# IDC2BNC.net
KiCad netlist of a schematic drawn in Altium Designer
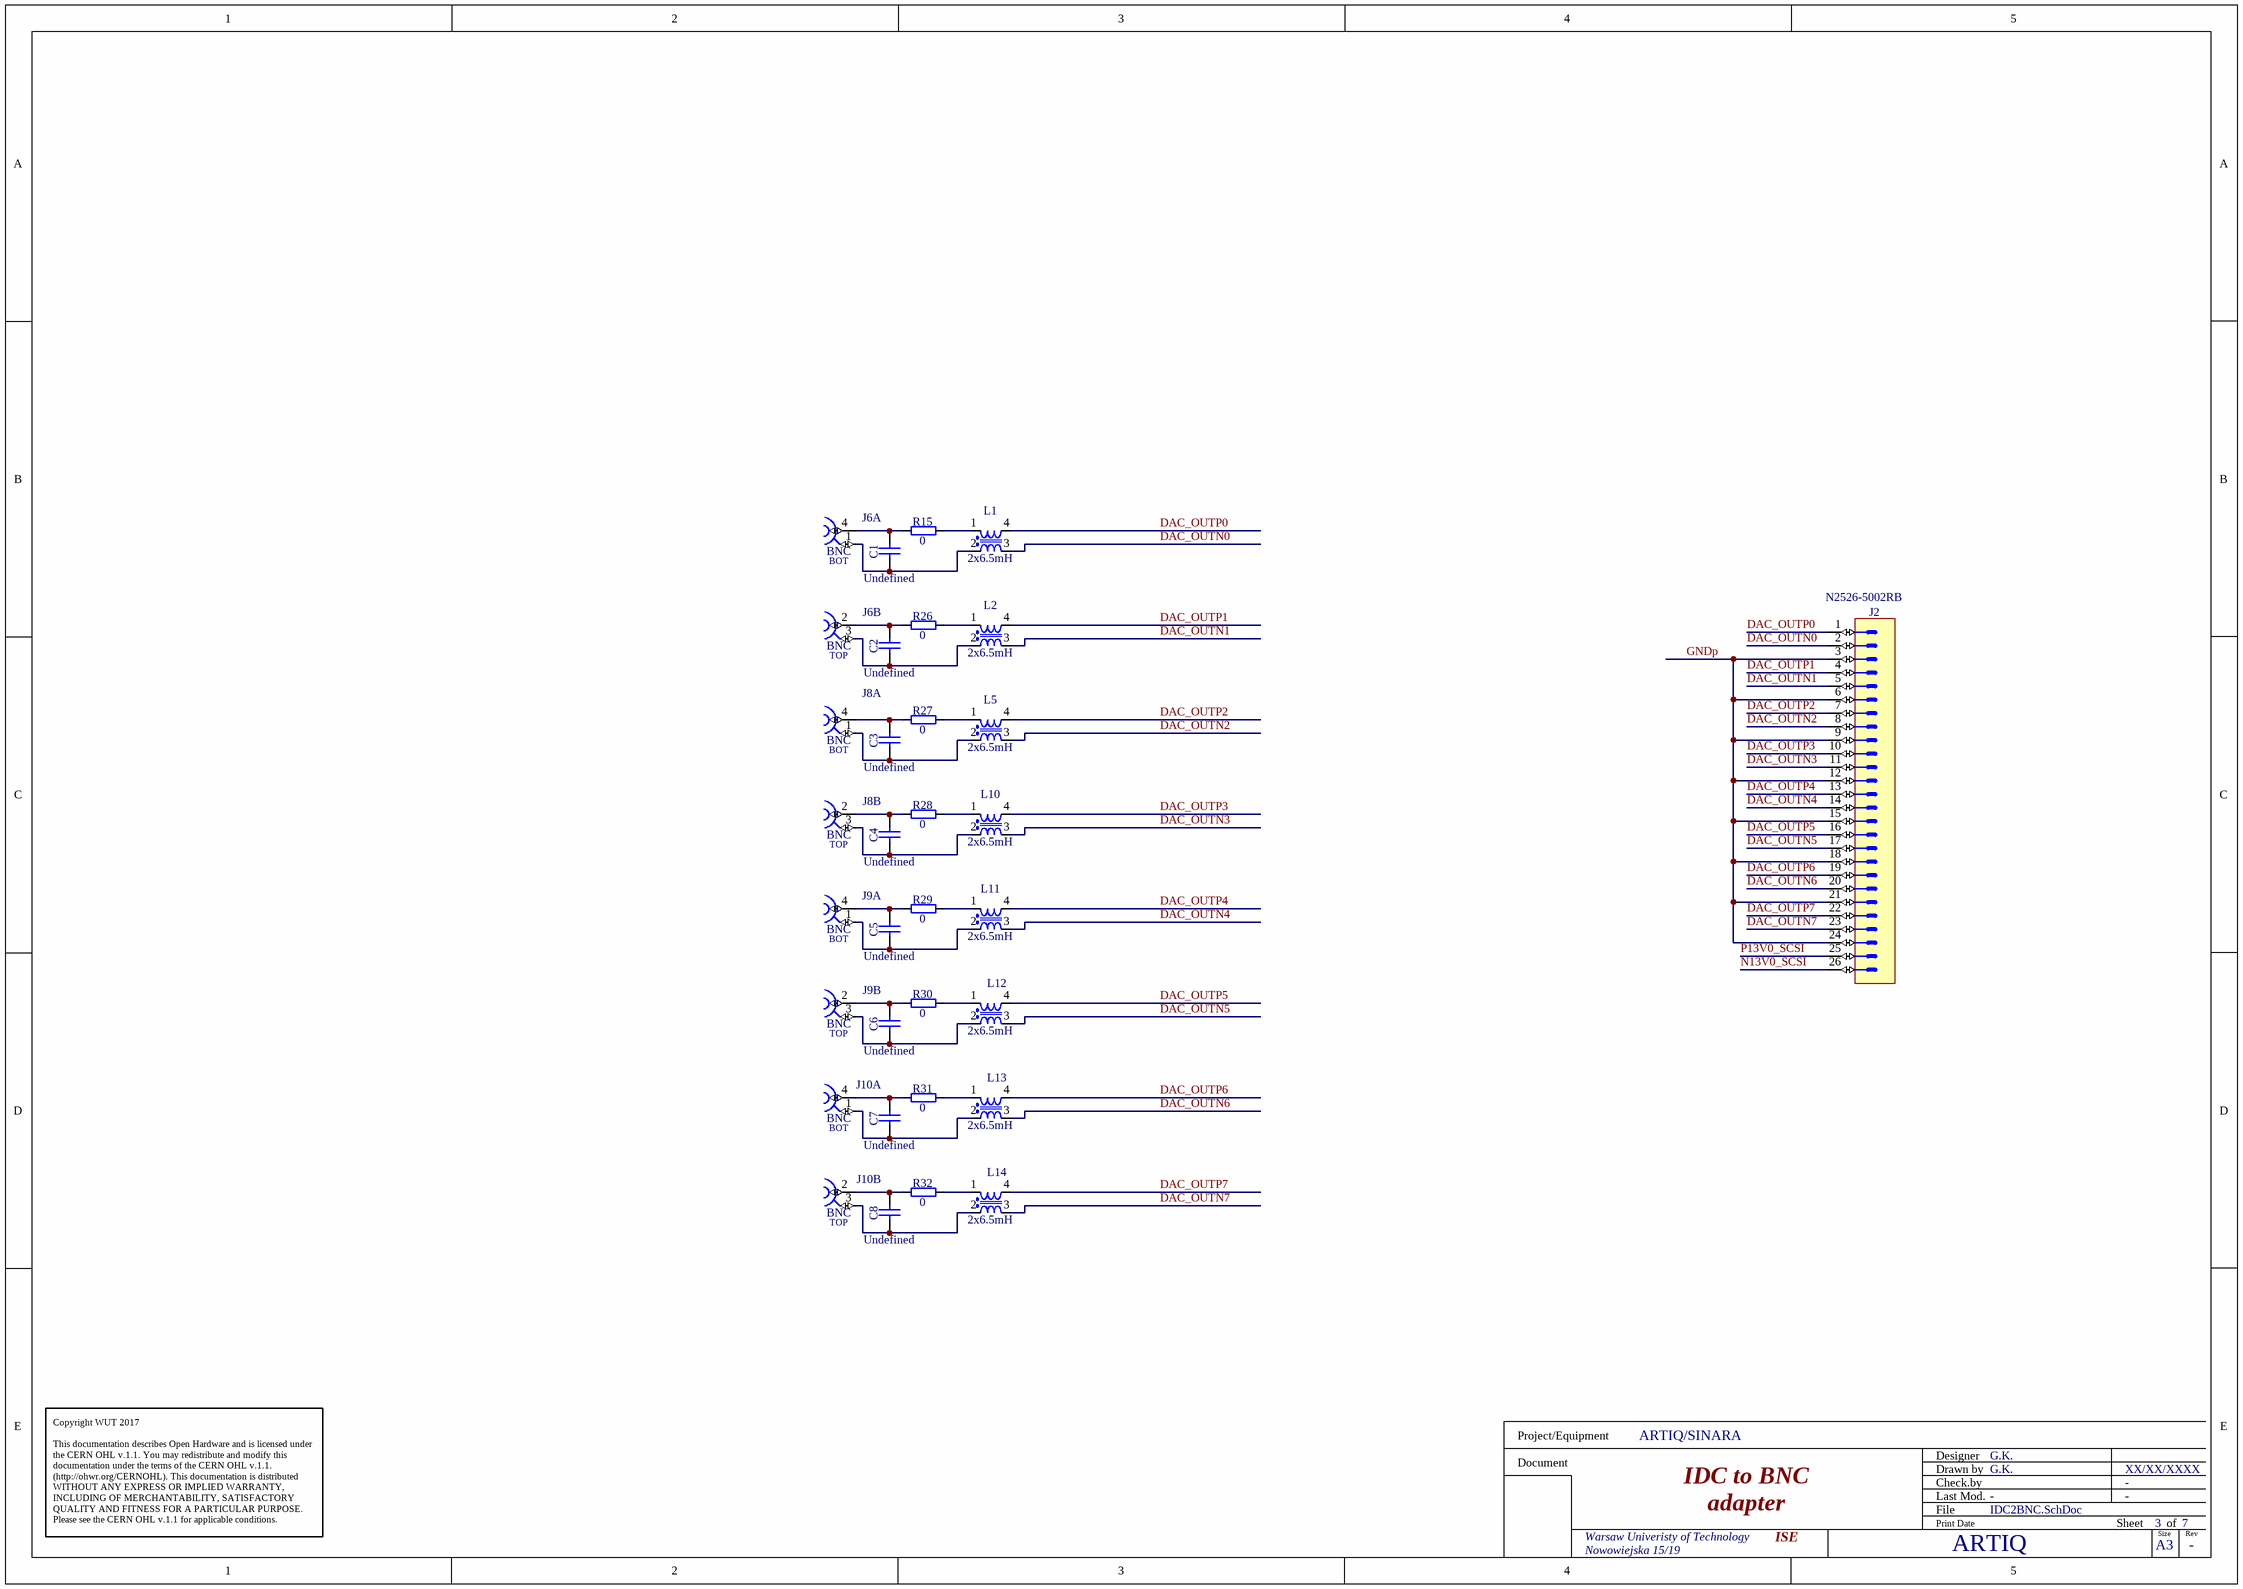
[diagram p0: IDC2BNC.SchDoc]

(export (version "E")
  (design (tool "Eeschema 10.0.6"))
  (components
    (comp (ref "C1")
      (value "Undefined")
      (footprint "CAPC2012X135N")
      (description "Non-polarised capacitor")
      (fields (field (name "PART NUMBER") "CC0805_NO-VALUE") (field (name "AUTHOR") "CERN DEM JLC"))
      (libsource (lib "Capacitors") (part "Capacitor - non polarized"))
    )
    (comp (ref "C2")
      (value "Undefined")
      (footprint "CAPC2012X135N")
      (description "Non-polarised capacitor")
      (fields (field (name "PART NUMBER") "CC0805_NO-VALUE") (field (name "AUTHOR") "CERN DEM JLC"))
      (libsource (lib "Capacitors") (part "Capacitor - non polarized"))
    )
    (comp (ref "C3")
      (value "Undefined")
      (footprint "CAPC2012X135N")
      (description "Non-polarised capacitor")
      (fields (field (name "PART NUMBER") "CC0805_NO-VALUE") (field (name "AUTHOR") "CERN DEM JLC"))
      (libsource (lib "Capacitors") (part "Capacitor - non polarized"))
    )
    (comp (ref "C4")
      (value "Undefined")
      (footprint "CAPC2012X135N")
      (description "Non-polarised capacitor")
      (fields (field (name "PART NUMBER") "CC0805_NO-VALUE") (field (name "AUTHOR") "CERN DEM JLC"))
      (libsource (lib "Capacitors") (part "Capacitor - non polarized"))
    )
    (comp (ref "C5")
      (value "Undefined")
      (footprint "CAPC2012X135N")
      (description "Non-polarised capacitor")
      (fields (field (name "PART NUMBER") "CC0805_NO-VALUE") (field (name "AUTHOR") "CERN DEM JLC"))
      (libsource (lib "Capacitors") (part "Capacitor - non polarized"))
    )
    (comp (ref "C6")
      (value "Undefined")
      (footprint "CAPC2012X135N")
      (description "Non-polarised capacitor")
      (fields (field (name "PART NUMBER") "CC0805_NO-VALUE") (field (name "AUTHOR") "CERN DEM JLC"))
      (libsource (lib "Capacitors") (part "Capacitor - non polarized"))
    )
    (comp (ref "C7")
      (value "Undefined")
      (footprint "CAPC2012X135N")
      (description "Non-polarised capacitor")
      (fields (field (name "PART NUMBER") "CC0805_NO-VALUE") (field (name "AUTHOR") "CERN DEM JLC"))
      (libsource (lib "Capacitors") (part "Capacitor - non polarized"))
    )
    (comp (ref "C8")
      (value "Undefined")
      (footprint "CAPC2012X135N")
      (description "Non-polarised capacitor")
      (fields (field (name "PART NUMBER") "CC0805_NO-VALUE") (field (name "AUTHOR") "CERN DEM JLC"))
      (libsource (lib "Capacitors") (part "Capacitor - non polarized"))
    )
    (comp (ref "J2")
      (value "Header 26")
      (footprint "3M_N2526-5002RB")
      (description "Connector 26 Male")
      (fields
        (field (name "PART NUMBER") "3M_N2526-5002RB")
        (field (name "MANUFACTURER") "3M")
        (field (name "MANUFACTURER PART NUMBER") "N2526-5002RB")
        (field (name "AUTHOR") "CERN DEM JLC")
      )
      (libsource (lib "Connectors") (part "Connector 26 Male"))
    )
    (comp (ref "J6")
      (value "BNC")
      (footprint "BOMAR_364A2595")
      (description "Dual Right Angle 50 Ohm BNC Jack, White Valox Case")
      (fields
        (field (name "PART NUMBER") "BOMAR_364A2595")
        (field (name "MANUFACTURER") "BOMAR INTERCONNECT")
        (field (name "AUTHOR") "CERN DEM JLC")
      )
      (libsource (lib "Connectors") (part "BOMAR_364A2595"))
    )
    (comp (ref "J8")
      (value "BNC")
      (footprint "BOMAR_364A2595")
      (description "Dual Right Angle 50 Ohm BNC Jack, White Valox Case")
      (fields
        (field (name "PART NUMBER") "BOMAR_364A2595")
        (field (name "MANUFACTURER") "BOMAR INTERCONNECT")
        (field (name "AUTHOR") "CERN DEM JLC")
      )
      (libsource (lib "Connectors") (part "BOMAR_364A2595"))
    )
    (comp (ref "J9")
      (value "BNC")
      (footprint "BOMAR_364A2595")
      (description "Dual Right Angle 50 Ohm BNC Jack, White Valox Case")
      (fields
        (field (name "PART NUMBER") "BOMAR_364A2595")
        (field (name "MANUFACTURER") "BOMAR INTERCONNECT")
        (field (name "AUTHOR") "CERN DEM JLC")
      )
      (libsource (lib "Connectors") (part "BOMAR_364A2595"))
    )
    (comp (ref "J10")
      (value "BNC")
      (footprint "BOMAR_364A2595")
      (description "Dual Right Angle 50 Ohm BNC Jack, White Valox Case")
      (fields
        (field (name "PART NUMBER") "BOMAR_364A2595")
        (field (name "MANUFACTURER") "BOMAR INTERCONNECT")
        (field (name "AUTHOR") "CERN DEM JLC")
      )
      (libsource (lib "Connectors") (part "BOMAR_364A2595"))
    )
    (comp (ref "L1")
      (value "2x6.5mH")
      (footprint "IND_WURTH_WE-SL2")
      (description "Inductor Common Mode")
      (fields
        (field (name "PART NUMBER") "IND_6.5MH_50%_WURTH_WE-SL2-744229")
        (field (name "POWER") "400mA")
        (field (name "AUTHOR") "CERN DEM JLC")
      )
      (libsource (lib "Inductors & Transformers") (part "Inductor Common Mode 1Dot-4 2Dot-3"))
    )
    (comp (ref "L2")
      (value "2x6.5mH")
      (footprint "IND_WURTH_WE-SL2")
      (description "Inductor Common Mode")
      (fields
        (field (name "PART NUMBER") "IND_6.5MH_50%_WURTH_WE-SL2-744229")
        (field (name "POWER") "400mA")
        (field (name "AUTHOR") "CERN DEM JLC")
      )
      (libsource (lib "Inductors & Transformers") (part "Inductor Common Mode 1Dot-4 2Dot-3"))
    )
    (comp (ref "L5")
      (value "2x6.5mH")
      (footprint "IND_WURTH_WE-SL2")
      (description "Inductor Common Mode")
      (fields
        (field (name "PART NUMBER") "IND_6.5MH_50%_WURTH_WE-SL2-744229")
        (field (name "POWER") "400mA")
        (field (name "AUTHOR") "CERN DEM JLC")
      )
      (libsource (lib "Inductors & Transformers") (part "Inductor Common Mode 1Dot-4 2Dot-3"))
    )
    (comp (ref "L10")
      (value "2x6.5mH")
      (footprint "IND_WURTH_WE-SL2")
      (description "Inductor Common Mode")
      (fields
        (field (name "PART NUMBER") "IND_6.5MH_50%_WURTH_WE-SL2-744229")
        (field (name "POWER") "400mA")
        (field (name "AUTHOR") "CERN DEM JLC")
      )
      (libsource (lib "Inductors & Transformers") (part "Inductor Common Mode 1Dot-4 2Dot-3"))
    )
    (comp (ref "L11")
      (value "2x6.5mH")
      (footprint "IND_WURTH_WE-SL2")
      (description "Inductor Common Mode")
      (fields
        (field (name "PART NUMBER") "IND_6.5MH_50%_WURTH_WE-SL2-744229")
        (field (name "POWER") "400mA")
        (field (name "AUTHOR") "CERN DEM JLC")
      )
      (libsource (lib "Inductors & Transformers") (part "Inductor Common Mode 1Dot-4 2Dot-3"))
    )
    (comp (ref "L12")
      (value "2x6.5mH")
      (footprint "IND_WURTH_WE-SL2")
      (description "Inductor Common Mode")
      (fields
        (field (name "PART NUMBER") "IND_6.5MH_50%_WURTH_WE-SL2-744229")
        (field (name "POWER") "400mA")
        (field (name "AUTHOR") "CERN DEM JLC")
      )
      (libsource (lib "Inductors & Transformers") (part "Inductor Common Mode 1Dot-4 2Dot-3"))
    )
    (comp (ref "L13")
      (value "2x6.5mH")
      (footprint "IND_WURTH_WE-SL2")
      (description "Inductor Common Mode")
      (fields
        (field (name "PART NUMBER") "IND_6.5MH_50%_WURTH_WE-SL2-744229")
        (field (name "POWER") "400mA")
        (field (name "AUTHOR") "CERN DEM JLC")
      )
      (libsource (lib "Inductors & Transformers") (part "Inductor Common Mode 1Dot-4 2Dot-3"))
    )
    (comp (ref "L14")
      (value "2x6.5mH")
      (footprint "IND_WURTH_WE-SL2")
      (description "Inductor Common Mode")
      (fields
        (field (name "PART NUMBER") "IND_6.5MH_50%_WURTH_WE-SL2-744229")
        (field (name "POWER") "400mA")
        (field (name "AUTHOR") "CERN DEM JLC")
      )
      (libsource (lib "Inductors & Transformers") (part "Inductor Common Mode 1Dot-4 2Dot-3"))
    )
    (comp (ref "R15")
      (value "0")
      (footprint "RESC1608X55N")
      (description "Resistor")
      (fields
        (field (name "PART NUMBER") "R0603_0R_JUMPER")
        (field (name "MANUFACTURER") "GENERIC")
        (field (name "AUTHOR") "CERN DEM JLC")
      )
      (libsource (lib "Resistors") (part "Resistor"))
    )
    (comp (ref "R26")
      (value "0")
      (footprint "RESC1608X55N")
      (description "Resistor")
      (fields
        (field (name "PART NUMBER") "R0603_0R_JUMPER")
        (field (name "MANUFACTURER") "GENERIC")
        (field (name "AUTHOR") "CERN DEM JLC")
      )
      (libsource (lib "Resistors") (part "Resistor"))
    )
    (comp (ref "R27")
      (value "0")
      (footprint "RESC1608X55N")
      (description "Resistor")
      (fields
        (field (name "PART NUMBER") "R0603_0R_JUMPER")
        (field (name "MANUFACTURER") "GENERIC")
        (field (name "AUTHOR") "CERN DEM JLC")
      )
      (libsource (lib "Resistors") (part "Resistor"))
    )
    (comp (ref "R28")
      (value "0")
      (footprint "RESC1608X55N")
      (description "Resistor")
      (fields
        (field (name "PART NUMBER") "R0603_0R_JUMPER")
        (field (name "MANUFACTURER") "GENERIC")
        (field (name "AUTHOR") "CERN DEM JLC")
      )
      (libsource (lib "Resistors") (part "Resistor"))
    )
    (comp (ref "R29")
      (value "0")
      (footprint "RESC1608X55N")
      (description "Resistor")
      (fields
        (field (name "PART NUMBER") "R0603_0R_JUMPER")
        (field (name "MANUFACTURER") "GENERIC")
        (field (name "AUTHOR") "CERN DEM JLC")
      )
      (libsource (lib "Resistors") (part "Resistor"))
    )
    (comp (ref "R30")
      (value "0")
      (footprint "RESC1608X55N")
      (description "Resistor")
      (fields
        (field (name "PART NUMBER") "R0603_0R_JUMPER")
        (field (name "MANUFACTURER") "GENERIC")
        (field (name "AUTHOR") "CERN DEM JLC")
      )
      (libsource (lib "Resistors") (part "Resistor"))
    )
    (comp (ref "R31")
      (value "0")
      (footprint "RESC1608X55N")
      (description "Resistor")
      (fields
        (field (name "PART NUMBER") "R0603_0R_JUMPER")
        (field (name "MANUFACTURER") "GENERIC")
        (field (name "AUTHOR") "CERN DEM JLC")
      )
      (libsource (lib "Resistors") (part "Resistor"))
    )
    (comp (ref "R32")
      (value "0")
      (footprint "RESC1608X55N")
      (description "Resistor")
      (fields
        (field (name "PART NUMBER") "R0603_0R_JUMPER")
        (field (name "MANUFACTURER") "GENERIC")
        (field (name "AUTHOR") "CERN DEM JLC")
      )
      (libsource (lib "Resistors") (part "Resistor"))
    )
  )
  (nets
    (net (code "1") (name "/DAC_OUTN0") (class "Default")
      (node (ref "J2") (pin "2") (pinfunction "2_2") (pintype "bidirectional"))
      (node (ref "L1") (pin "3") (pinfunction "3_3") (pintype "passive"))
    )
    (net (code "2") (name "/DAC_OUTN1") (class "Default")
      (node (ref "J2") (pin "5") (pinfunction "5_5") (pintype "bidirectional"))
      (node (ref "L2") (pin "3") (pinfunction "3_3") (pintype "passive"))
    )
    (net (code "3") (name "/DAC_OUTN2") (class "Default")
      (node (ref "J2") (pin "8") (pinfunction "8_8") (pintype "bidirectional"))
      (node (ref "L5") (pin "3") (pinfunction "3_3") (pintype "passive"))
    )
    (net (code "4") (name "/DAC_OUTN3") (class "Default")
      (node (ref "J2") (pin "11") (pinfunction "11_11") (pintype "bidirectional"))
      (node (ref "L10") (pin "3") (pinfunction "3_3") (pintype "passive"))
    )
    (net (code "5") (name "/DAC_OUTN4") (class "Default")
      (node (ref "J2") (pin "14") (pinfunction "14_14") (pintype "bidirectional"))
      (node (ref "L11") (pin "3") (pinfunction "3_3") (pintype "passive"))
    )
    (net (code "6") (name "/DAC_OUTN5") (class "Default")
      (node (ref "J2") (pin "17") (pinfunction "17_17") (pintype "bidirectional"))
      (node (ref "L12") (pin "3") (pinfunction "3_3") (pintype "passive"))
    )
    (net (code "7") (name "/DAC_OUTN6") (class "Default")
      (node (ref "J2") (pin "20") (pinfunction "20_20") (pintype "bidirectional"))
      (node (ref "L13") (pin "3") (pinfunction "3_3") (pintype "passive"))
    )
    (net (code "8") (name "/DAC_OUTN7") (class "Default")
      (node (ref "J2") (pin "23") (pinfunction "23_23") (pintype "bidirectional"))
      (node (ref "L14") (pin "3") (pinfunction "3_3") (pintype "passive"))
    )
    (net (code "9") (name "/DAC_OUTP0") (class "Default")
      (node (ref "J2") (pin "1") (pinfunction "1_1") (pintype "bidirectional"))
      (node (ref "L1") (pin "4") (pinfunction "4_4") (pintype "passive"))
    )
    (net (code "10") (name "/DAC_OUTP1") (class "Default")
      (node (ref "J2") (pin "4") (pinfunction "4_4") (pintype "bidirectional"))
      (node (ref "L2") (pin "4") (pinfunction "4_4") (pintype "passive"))
    )
    (net (code "11") (name "/DAC_OUTP2") (class "Default")
      (node (ref "J2") (pin "7") (pinfunction "7_7") (pintype "bidirectional"))
      (node (ref "L5") (pin "4") (pinfunction "4_4") (pintype "passive"))
    )
    (net (code "12") (name "/DAC_OUTP3") (class "Default")
      (node (ref "J2") (pin "10") (pinfunction "10_10") (pintype "bidirectional"))
      (node (ref "L10") (pin "4") (pinfunction "4_4") (pintype "passive"))
    )
    (net (code "13") (name "/DAC_OUTP4") (class "Default")
      (node (ref "J2") (pin "13") (pinfunction "13_13") (pintype "bidirectional"))
      (node (ref "L11") (pin "4") (pinfunction "4_4") (pintype "passive"))
    )
    (net (code "14") (name "/DAC_OUTP5") (class "Default")
      (node (ref "J2") (pin "16") (pinfunction "16_16") (pintype "bidirectional"))
      (node (ref "L12") (pin "4") (pinfunction "4_4") (pintype "passive"))
    )
    (net (code "15") (name "/DAC_OUTP6") (class "Default")
      (node (ref "J2") (pin "19") (pinfunction "19_19") (pintype "bidirectional"))
      (node (ref "L13") (pin "4") (pinfunction "4_4") (pintype "passive"))
    )
    (net (code "16") (name "/DAC_OUTP7") (class "Default")
      (node (ref "J2") (pin "22") (pinfunction "22_22") (pintype "bidirectional"))
      (node (ref "L14") (pin "4") (pinfunction "4_4") (pintype "passive"))
    )
    (net (code "17") (name "/GNDp") (class "Default")
      (node (ref "J2") (pin "12") (pinfunction "12_12") (pintype "bidirectional"))
      (node (ref "J2") (pin "15") (pinfunction "15_15") (pintype "bidirectional"))
      (node (ref "J2") (pin "18") (pinfunction "18_18") (pintype "bidirectional"))
      (node (ref "J2") (pin "21") (pinfunction "21_21") (pintype "bidirectional"))
      (node (ref "J2") (pin "24") (pinfunction "24_24") (pintype "bidirectional"))
      (node (ref "J2") (pin "3") (pinfunction "3_3") (pintype "bidirectional"))
      (node (ref "J2") (pin "6") (pinfunction "6_6") (pintype "bidirectional"))
      (node (ref "J2") (pin "9") (pinfunction "9_9") (pintype "bidirectional"))
    )
    (net (code "18") (name "/N13V0_SCSI") (class "Default")
      (node (ref "J2") (pin "26") (pinfunction "26_26") (pintype "bidirectional"))
    )
    (net (code "19") (name "/P13V0_SCSI") (class "Default")
      (node (ref "J2") (pin "25") (pinfunction "25_25") (pintype "bidirectional"))
    )
    (net (code "20") (name "Net-(C1-Pad1)") (class "Default")
      (node (ref "C1") (pin "1") (pinfunction "1_1") (pintype "passive"))
      (node (ref "J6") (pin "1") (pinfunction "1_1") (pintype "bidirectional"))
      (node (ref "L1") (pin "2") (pinfunction "2_2") (pintype "passive"))
    )
    (net (code "21") (name "Net-(C1-Pad2)") (class "Default")
      (node (ref "C1") (pin "2") (pinfunction "2_2") (pintype "passive"))
      (node (ref "J6") (pin "4") (pinfunction "4_4") (pintype "bidirectional"))
      (node (ref "R15") (pin "1") (pinfunction "1_1") (pintype "passive"))
    )
    (net (code "22") (name "Net-(C2-Pad1)") (class "Default")
      (node (ref "C2") (pin "1") (pinfunction "1_1") (pintype "passive"))
      (node (ref "J6") (pin "3") (pinfunction "3_3") (pintype "bidirectional"))
      (node (ref "L2") (pin "2") (pinfunction "2_2") (pintype "passive"))
    )
    (net (code "23") (name "Net-(C2-Pad2)") (class "Default")
      (node (ref "C2") (pin "2") (pinfunction "2_2") (pintype "passive"))
      (node (ref "J6") (pin "2") (pinfunction "2_2") (pintype "bidirectional"))
      (node (ref "R26") (pin "1") (pinfunction "1_1") (pintype "passive"))
    )
    (net (code "24") (name "Net-(C3-Pad1)") (class "Default")
      (node (ref "C3") (pin "1") (pinfunction "1_1") (pintype "passive"))
      (node (ref "J8") (pin "1") (pinfunction "1_1") (pintype "bidirectional"))
      (node (ref "L5") (pin "2") (pinfunction "2_2") (pintype "passive"))
    )
    (net (code "25") (name "Net-(C3-Pad2)") (class "Default")
      (node (ref "C3") (pin "2") (pinfunction "2_2") (pintype "passive"))
      (node (ref "J8") (pin "4") (pinfunction "4_4") (pintype "bidirectional"))
      (node (ref "R27") (pin "1") (pinfunction "1_1") (pintype "passive"))
    )
    (net (code "26") (name "Net-(C4-Pad1)") (class "Default")
      (node (ref "C4") (pin "1") (pinfunction "1_1") (pintype "passive"))
      (node (ref "J8") (pin "3") (pinfunction "3_3") (pintype "bidirectional"))
      (node (ref "L10") (pin "2") (pinfunction "2_2") (pintype "passive"))
    )
    (net (code "27") (name "Net-(C4-Pad2)") (class "Default")
      (node (ref "C4") (pin "2") (pinfunction "2_2") (pintype "passive"))
      (node (ref "J8") (pin "2") (pinfunction "2_2") (pintype "bidirectional"))
      (node (ref "R28") (pin "1") (pinfunction "1_1") (pintype "passive"))
    )
    (net (code "28") (name "Net-(C5-Pad1)") (class "Default")
      (node (ref "C5") (pin "1") (pinfunction "1_1") (pintype "passive"))
      (node (ref "J9") (pin "1") (pinfunction "1_1") (pintype "bidirectional"))
      (node (ref "L11") (pin "2") (pinfunction "2_2") (pintype "passive"))
    )
    (net (code "29") (name "Net-(C5-Pad2)") (class "Default")
      (node (ref "C5") (pin "2") (pinfunction "2_2") (pintype "passive"))
      (node (ref "J9") (pin "4") (pinfunction "4_4") (pintype "bidirectional"))
      (node (ref "R29") (pin "1") (pinfunction "1_1") (pintype "passive"))
    )
    (net (code "30") (name "Net-(C6-Pad1)") (class "Default")
      (node (ref "C6") (pin "1") (pinfunction "1_1") (pintype "passive"))
      (node (ref "J9") (pin "3") (pinfunction "3_3") (pintype "bidirectional"))
      (node (ref "L12") (pin "2") (pinfunction "2_2") (pintype "passive"))
    )
    (net (code "31") (name "Net-(C6-Pad2)") (class "Default")
      (node (ref "C6") (pin "2") (pinfunction "2_2") (pintype "passive"))
      (node (ref "J9") (pin "2") (pinfunction "2_2") (pintype "bidirectional"))
      (node (ref "R30") (pin "1") (pinfunction "1_1") (pintype "passive"))
    )
    (net (code "32") (name "Net-(C7-Pad1)") (class "Default")
      (node (ref "C7") (pin "1") (pinfunction "1_1") (pintype "passive"))
      (node (ref "J10") (pin "1") (pinfunction "1_1") (pintype "bidirectional"))
      (node (ref "L13") (pin "2") (pinfunction "2_2") (pintype "passive"))
    )
    (net (code "33") (name "Net-(C7-Pad2)") (class "Default")
      (node (ref "C7") (pin "2") (pinfunction "2_2") (pintype "passive"))
      (node (ref "J10") (pin "4") (pinfunction "4_4") (pintype "bidirectional"))
      (node (ref "R31") (pin "1") (pinfunction "1_1") (pintype "passive"))
    )
    (net (code "34") (name "Net-(C8-Pad1)") (class "Default")
      (node (ref "C8") (pin "1") (pinfunction "1_1") (pintype "passive"))
      (node (ref "J10") (pin "3") (pinfunction "3_3") (pintype "bidirectional"))
      (node (ref "L14") (pin "2") (pinfunction "2_2") (pintype "passive"))
    )
    (net (code "35") (name "Net-(C8-Pad2)") (class "Default")
      (node (ref "C8") (pin "2") (pinfunction "2_2") (pintype "passive"))
      (node (ref "J10") (pin "2") (pinfunction "2_2") (pintype "bidirectional"))
      (node (ref "R32") (pin "1") (pinfunction "1_1") (pintype "passive"))
    )
    (net (code "36") (name "Net-(L1-Pad1)") (class "Default")
      (node (ref "L1") (pin "1") (pinfunction "1_1") (pintype "passive"))
      (node (ref "R15") (pin "2") (pinfunction "2_2") (pintype "passive"))
    )
    (net (code "37") (name "Net-(L2-Pad1)") (class "Default")
      (node (ref "L2") (pin "1") (pinfunction "1_1") (pintype "passive"))
      (node (ref "R26") (pin "2") (pinfunction "2_2") (pintype "passive"))
    )
    (net (code "38") (name "Net-(L5-Pad1)") (class "Default")
      (node (ref "L5") (pin "1") (pinfunction "1_1") (pintype "passive"))
      (node (ref "R27") (pin "2") (pinfunction "2_2") (pintype "passive"))
    )
    (net (code "39") (name "Net-(L10-Pad1)") (class "Default")
      (node (ref "L10") (pin "1") (pinfunction "1_1") (pintype "passive"))
      (node (ref "R28") (pin "2") (pinfunction "2_2") (pintype "passive"))
    )
    (net (code "40") (name "Net-(L11-Pad1)") (class "Default")
      (node (ref "L11") (pin "1") (pinfunction "1_1") (pintype "passive"))
      (node (ref "R29") (pin "2") (pinfunction "2_2") (pintype "passive"))
    )
    (net (code "41") (name "Net-(L12-Pad1)") (class "Default")
      (node (ref "L12") (pin "1") (pinfunction "1_1") (pintype "passive"))
      (node (ref "R30") (pin "2") (pinfunction "2_2") (pintype "passive"))
    )
    (net (code "42") (name "Net-(L13-Pad1)") (class "Default")
      (node (ref "L13") (pin "1") (pinfunction "1_1") (pintype "passive"))
      (node (ref "R31") (pin "2") (pinfunction "2_2") (pintype "passive"))
    )
    (net (code "43") (name "Net-(L14-Pad1)") (class "Default")
      (node (ref "L14") (pin "1") (pinfunction "1_1") (pintype "passive"))
      (node (ref "R32") (pin "2") (pinfunction "2_2") (pintype "passive"))
    )
  )
)
